# ATmega.net
KiCad netlist of a schematic drawn in Altium Designer
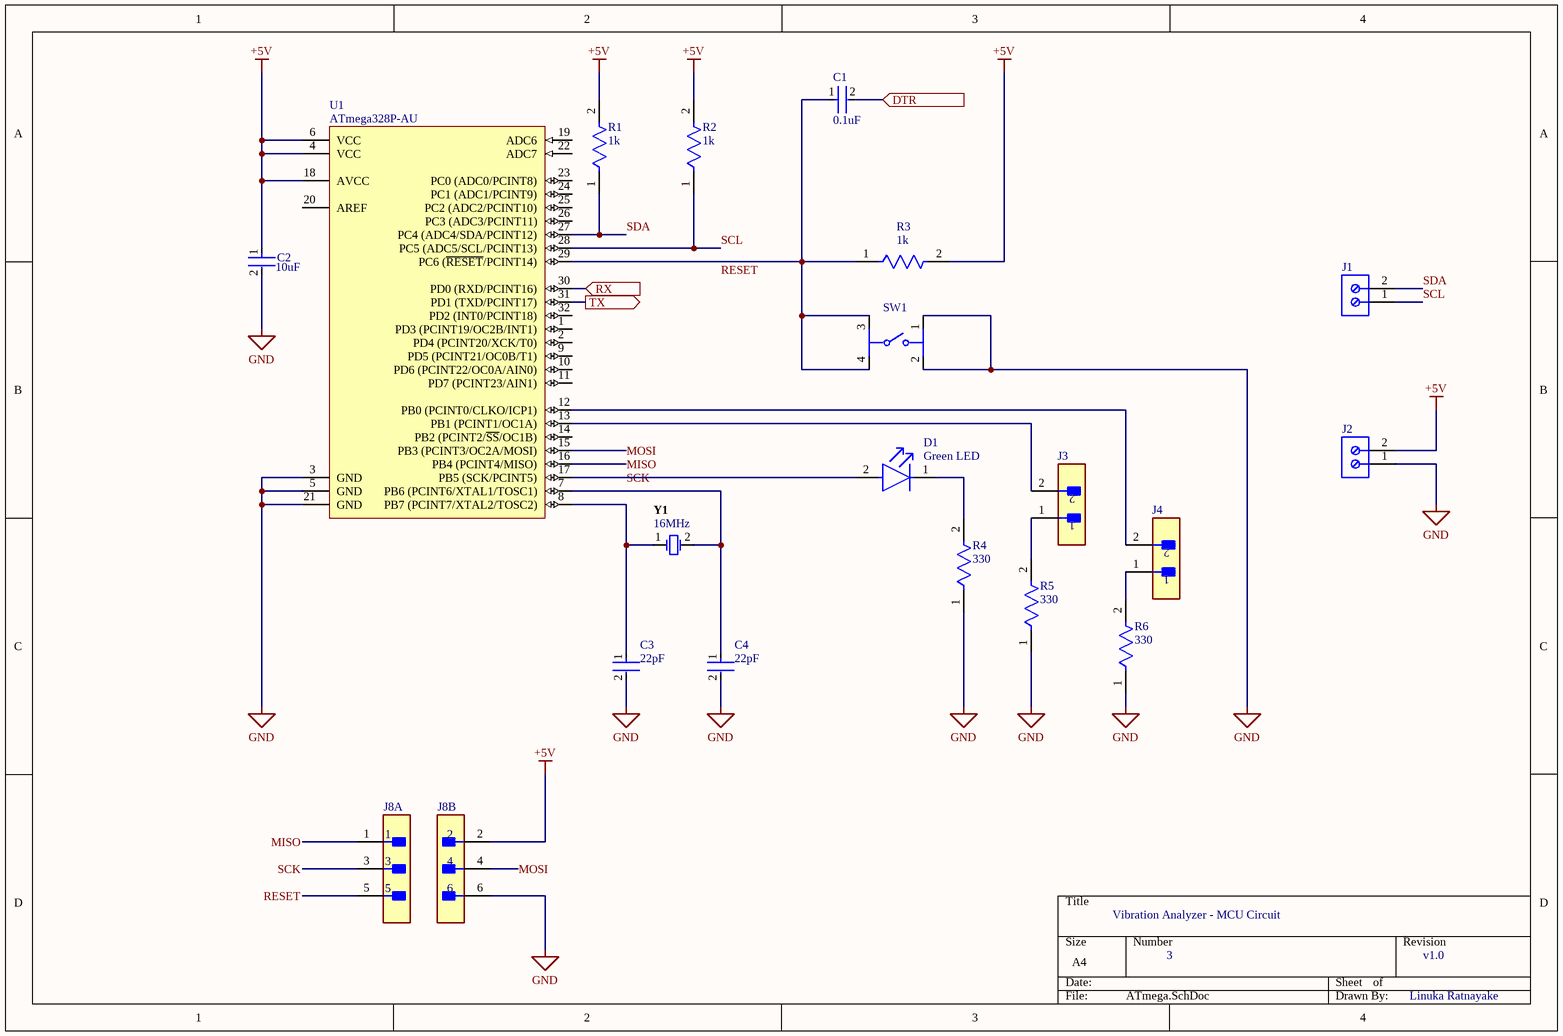
[diagram p0: ATmega.SchDoc]

(export (version "E")
  (design (tool "Eeschema 10.0.6"))
  (components
    (comp (ref "C1")
      (value "GRM31M1X1H104JA01L")
      (footprint "FP-GRM31M-0_15-IPC_A")
      (fields
        (field (name "VOLTAGE") "50V")
        (field (name "TOLERANCE") "5%")
        (field (name "CAPACITANCE") "0.1uF")
      )
      (libsource (lib "Altium Content Vault") (part "b4654b650e69147ec39a6b967a45e02"))
    )
    (comp (ref "C2")
      (value "GRM31M1X1H104JA01L")
      (footprint "FP-GRM31M-0_15-IPC_A")
      (fields
        (field (name "VOLTAGE") "50V")
        (field (name "TOLERANCE") "5%")
        (field (name "CAPACITANCE") "10uF")
      )
      (libsource (lib "Altium Content Vault") (part "b4654b650e69147ec39a6b967a45e02"))
    )
    (comp (ref "C3")
      (value "GRM31M1X1H104JA01L")
      (footprint "FP-GRM31M-0_15-IPC_A")
      (fields
        (field (name "VOLTAGE") "50V")
        (field (name "TOLERANCE") "5%")
        (field (name "CAPACITANCE") "22pF")
      )
      (libsource (lib "Altium Content Vault") (part "b4654b650e69147ec39a6b967a45e02"))
    )
    (comp (ref "C4")
      (value "GRM31M1X1H104JA01L")
      (footprint "FP-GRM31M-0_15-IPC_A")
      (fields
        (field (name "VOLTAGE") "50V")
        (field (name "TOLERANCE") "5%")
        (field (name "CAPACITANCE") "22pF")
      )
      (libsource (lib "Altium Content Vault") (part "b4654b650e69147ec39a6b967a45e02"))
    )
    (comp (ref "D1")
      (value "HSMG-C150")
      (footprint "FP-HSMG-C150-MFG")
      (description "LED GREEN DIFFUSED 1206 SMD")
      (fields
        (field (name "MANUFACTURER") "Broadcom")
        (field (name "OCTOPART") "https://octopart.com/hsmg-c150-broadcom-71131304")
        (field (name "COLOR") "Green LED")
      )
      (libsource (lib "Altium Content Vault") (part "8706943c75ba83719d021d2fdc84c58"))
    )
    (comp (ref "J1")
      (value "691214110002")
      (footprint "691214110002")
      (fields (field (name "VOLTAGE") "300V"))
      (libsource (lib "Altium Content Vault") (part "TBL - 1R - 02P - Screw"))
    )
    (comp (ref "J2")
      (value "691214110002")
      (footprint "691214110002")
      (fields (field (name "VOLTAGE") "300V"))
      (libsource (lib "Altium Content Vault") (part "TBL - 1R - 02P - Screw"))
    )
    (comp (ref "J3")
      (value "B2B-XH-A(LF)(SN)")
      (footprint "FP-B2B-XH-A_LF_SN-MFG")
      (description "CONN HEADER VERT 2POS 2.5MM")
      (libsource (lib "Altium Content Vault") (part "3bc925449376181038e59eaffc5286c"))
    )
    (comp (ref "J4")
      (value "B2B-XH-A(LF)(SN)")
      (footprint "FP-B2B-XH-A_LF_SN-MFG")
      (description "CONN HEADER VERT 2POS 2.5MM")
      (libsource (lib "Altium Content Vault") (part "3bc925449376181038e59eaffc5286c"))
    )
    (comp (ref "J8")
      (value "M20-9980346")
      (footprint "FP-M20-9980346-MFG")
      (description "2.54mm Pitch 6 Way 2 Row Straight PCB Header, Solder Termination, 3A")
      (fields (field (name "MANUFACTURER") "Harwin"))
      (libsource (lib "") (part "2654a11fb13586ecb194516b1c997bc_1"))
    )
    (comp (ref "R1")
      (value "MCR18EZPF30R0")
      (footprint "FP-MCR18-IPC_B")
      (description "Thick Film Chip Resistor, 1206, 30Ω, 1%, 100ppm/°C, 0.25W, 200V")
      (fields (field (name "RESISTANCE") "1k") (field (name "TOLERANCE") "1%"))
      (libsource (lib "Altium Content Vault") (part "1029c3af85768c4190bb7ad29bc67b5"))
    )
    (comp (ref "R2")
      (value "MCR18EZPF30R0")
      (footprint "FP-MCR18-IPC_B")
      (description "Thick Film Chip Resistor, 1206, 30Ω, 1%, 100ppm/°C, 0.25W, 200V")
      (fields (field (name "RESISTANCE") "1k") (field (name "TOLERANCE") "1%"))
      (libsource (lib "Altium Content Vault") (part "1029c3af85768c4190bb7ad29bc67b5"))
    )
    (comp (ref "R3")
      (value "MCR18EZPF30R0")
      (footprint "FP-MCR18-IPC_B")
      (description "Thick Film Chip Resistor, 1206, 30Ω, 1%, 100ppm/°C, 0.25W, 200V")
      (fields (field (name "RESISTANCE") "1k") (field (name "TOLERANCE") "1%"))
      (libsource (lib "Altium Content Vault") (part "1029c3af85768c4190bb7ad29bc67b5"))
    )
    (comp (ref "R4")
      (value "MCR18EZPF30R0")
      (footprint "FP-MCR18-IPC_B")
      (description "Thick Film Chip Resistor, 1206, 30Ω, 1%, 100ppm/°C, 0.25W, 200V")
      (fields (field (name "RESISTANCE") "330") (field (name "TOLERANCE") "1%"))
      (libsource (lib "Altium Content Vault") (part "1029c3af85768c4190bb7ad29bc67b5"))
    )
    (comp (ref "R5")
      (value "MCR18EZPF30R0")
      (footprint "FP-MCR18-IPC_B")
      (description "Thick Film Chip Resistor, 1206, 30Ω, 1%, 100ppm/°C, 0.25W, 200V")
      (fields (field (name "RESISTANCE") "330") (field (name "TOLERANCE") "1%"))
      (libsource (lib "Altium Content Vault") (part "1029c3af85768c4190bb7ad29bc67b5"))
    )
    (comp (ref "R6")
      (value "MCR18EZPF30R0")
      (footprint "FP-MCR18-IPC_B")
      (description "Thick Film Chip Resistor, 1206, 30Ω, 1%, 100ppm/°C, 0.25W, 200V")
      (fields (field (name "RESISTANCE") "330") (field (name "TOLERANCE") "1%"))
      (libsource (lib "Altium Content Vault") (part "1029c3af85768c4190bb7ad29bc67b5"))
    )
    (comp (ref "SW1")
      (value "PTS645SM43SMTR92LFS")
      (footprint "FP-PTS645SM43SMTR92LFS-MFG")
      (description "SWITCH TACTILE SPST-NO 0.05A 12V")
      (libsource (lib "Altium Content Vault") (part "1adf0dd01260c80cf25a44bfd6b99ba"))
    )
    (comp (ref "U1")
      (value "ATmega328P-AU")
      (footprint "32A_M")
      (libsource (lib "Altium Content Vault") (part "MC-8B-ATM48-SQ32"))
    )
    (comp (ref "Y1")
      (value "FOXSLF/160-20")
      (footprint "FOX-FOXSLF160-20")
      (description "Resistance Weld Thru-Hole Crystal, 16 MHz, -20 to 70 degC, 2-Pin THD, RoHS, Bulk")
      (fields (field (name "TOLERANCE") "1%") (field (name "FREQUENCY") "16MHz"))
      (libsource (lib "Altium Content Vault") (part "XTAL-1-2-2"))
    )
  )
  (nets
    (net (code "1") (name "+5V") (class "Default")
      (node (ref "C2") (pin "1") (pinfunction "1_1") (pintype "passive"))
      (node (ref "J2") (pin "2") (pinfunction "2_2") (pintype "passive"))
      (node (ref "J8") (pin "2") (pinfunction "2_2") (pintype "passive"))
      (node (ref "R1") (pin "2") (pinfunction "2_2") (pintype "passive"))
      (node (ref "R2") (pin "2") (pinfunction "2_2") (pintype "passive"))
      (node (ref "R3") (pin "2") (pinfunction "2_2") (pintype "passive"))
      (node (ref "U1") (pin "18") (pinfunction "AVCC_18") (pintype "power_in"))
      (node (ref "U1") (pin "4") (pinfunction "VCC_4") (pintype "power_in"))
      (node (ref "U1") (pin "6") (pinfunction "VCC_6") (pintype "power_in"))
    )
    (net (code "2") (name "/DTR") (class "Default")
      (node (ref "C1") (pin "2") (pinfunction "2_2") (pintype "passive"))
    )
    (net (code "3") (name "/MISO") (class "Default")
      (node (ref "J8") (pin "1") (pinfunction "1_1") (pintype "passive"))
      (node (ref "U1") (pin "16") (pinfunction "PB4_(PCINT4/MISO)_16") (pintype "bidirectional"))
    )
    (net (code "4") (name "/MOSI") (class "Default")
      (node (ref "J8") (pin "4") (pinfunction "4_4") (pintype "passive"))
      (node (ref "U1") (pin "15") (pinfunction "PB3_(PCINT3/OC2A/MOSI)_15") (pintype "bidirectional"))
    )
    (net (code "5") (name "/RESET") (class "Default")
      (node (ref "C1") (pin "1") (pinfunction "1_1") (pintype "passive"))
      (node (ref "J8") (pin "5") (pinfunction "5_5") (pintype "passive"))
      (node (ref "R3") (pin "1") (pinfunction "1_1") (pintype "passive"))
      (node (ref "SW1") (pin "3") (pinfunction "3_3") (pintype "passive"))
      (node (ref "SW1") (pin "4") (pinfunction "4_4") (pintype "passive"))
      (node (ref "U1") (pin "29") (pinfunction "PC6_(~{RESET}/PCINT14)_29") (pintype "bidirectional"))
    )
    (net (code "6") (name "/RX") (class "Default")
      (node (ref "U1") (pin "30") (pinfunction "PD0_(RXD/PCINT16)_30") (pintype "bidirectional"))
    )
    (net (code "7") (name "/SCK") (class "Default")
      (node (ref "D1") (pin "2") (pinfunction "A_2") (pintype "passive"))
      (node (ref "J8") (pin "3") (pinfunction "3_3") (pintype "passive"))
      (node (ref "U1") (pin "17") (pinfunction "PB5_(SCK/PCINT5)_17") (pintype "bidirectional"))
    )
    (net (code "8") (name "/SCL") (class "Default")
      (node (ref "J1") (pin "1") (pinfunction "1_1") (pintype "passive"))
      (node (ref "R2") (pin "1") (pinfunction "1_1") (pintype "passive"))
      (node (ref "U1") (pin "28") (pinfunction "PC5_(ADC5/SCL/PCINT13)_28") (pintype "bidirectional"))
    )
    (net (code "9") (name "/SDA") (class "Default")
      (node (ref "J1") (pin "2") (pinfunction "2_2") (pintype "passive"))
      (node (ref "R1") (pin "1") (pinfunction "1_1") (pintype "passive"))
      (node (ref "U1") (pin "27") (pinfunction "PC4_(ADC4/SDA/PCINT12)_27") (pintype "bidirectional"))
    )
    (net (code "10") (name "/TX") (class "Default")
      (node (ref "U1") (pin "31") (pinfunction "PD1_(TXD/PCINT17)_31") (pintype "bidirectional"))
    )
    (net (code "11") (name "GND") (class "Default")
      (node (ref "C2") (pin "2") (pinfunction "2_2") (pintype "passive"))
      (node (ref "C3") (pin "2") (pinfunction "2_2") (pintype "passive"))
      (node (ref "C4") (pin "2") (pinfunction "2_2") (pintype "passive"))
      (node (ref "J2") (pin "1") (pinfunction "1_1") (pintype "passive"))
      (node (ref "J8") (pin "6") (pinfunction "6_6") (pintype "passive"))
      (node (ref "R4") (pin "1") (pinfunction "1_1") (pintype "passive"))
      (node (ref "R5") (pin "1") (pinfunction "1_1") (pintype "passive"))
      (node (ref "R6") (pin "1") (pinfunction "1_1") (pintype "passive"))
      (node (ref "SW1") (pin "1") (pinfunction "1_1") (pintype "passive"))
      (node (ref "SW1") (pin "2") (pinfunction "2_2") (pintype "passive"))
      (node (ref "U1") (pin "21") (pinfunction "GND_21") (pintype "power_in"))
      (node (ref "U1") (pin "3") (pinfunction "GND_3") (pintype "power_in"))
      (node (ref "U1") (pin "5") (pinfunction "GND_5") (pintype "power_in"))
    )
    (net (code "12") (name "Net-(D1-C)") (class "Default")
      (node (ref "D1") (pin "1") (pinfunction "C_1") (pintype "passive"))
      (node (ref "R4") (pin "2") (pinfunction "2_2") (pintype "passive"))
    )
    (net (code "13") (name "Net-(J3-Pad1)") (class "Default")
      (node (ref "J3") (pin "1") (pinfunction "1_1") (pintype "passive"))
      (node (ref "R5") (pin "2") (pinfunction "2_2") (pintype "passive"))
    )
    (net (code "14") (name "Net-(J4-Pad1)") (class "Default")
      (node (ref "J4") (pin "1") (pinfunction "1_1") (pintype "passive"))
      (node (ref "R6") (pin "2") (pinfunction "2_2") (pintype "passive"))
    )
    (net (code "15") (name "Net-(U1-PB0_(PCINT0{slash}CLKO{slash}ICP1))") (class "Default")
      (node (ref "J4") (pin "2") (pinfunction "2_2") (pintype "passive"))
      (node (ref "U1") (pin "12") (pinfunction "PB0_(PCINT0/CLKO/ICP1)_12") (pintype "bidirectional"))
    )
    (net (code "16") (name "Net-(U1-PB1_(PCINT1{slash}OC1A))") (class "Default")
      (node (ref "J3") (pin "2") (pinfunction "2_2") (pintype "passive"))
      (node (ref "U1") (pin "13") (pinfunction "PB1_(PCINT1/OC1A)_13") (pintype "bidirectional"))
    )
    (net (code "17") (name "Net-(U1-PB6_(PCINT6{slash}XTAL1{slash}TOSC1))") (class "Default")
      (node (ref "C4") (pin "1") (pinfunction "1_1") (pintype "passive"))
      (node (ref "U1") (pin "7") (pinfunction "PB6_(PCINT6/XTAL1/TOSC1)_7") (pintype "bidirectional"))
      (node (ref "Y1") (pin "2") (pinfunction "2_2") (pintype "passive"))
    )
    (net (code "18") (name "Net-(U1-PB7_(PCINT7{slash}XTAL2{slash}TOSC2))") (class "Default")
      (node (ref "C3") (pin "1") (pinfunction "1_1") (pintype "passive"))
      (node (ref "U1") (pin "8") (pinfunction "PB7_(PCINT7/XTAL2/TOSC2)_8") (pintype "bidirectional"))
      (node (ref "Y1") (pin "1") (pinfunction "1_1") (pintype "passive"))
    )
    (net (code "19") (name "unconnected-(U1-ADC6-Pad19)") (class "Default")
      (node (ref "U1") (pin "19") (pinfunction "ADC6_19") (pintype "input"))
    )
    (net (code "20") (name "unconnected-(U1-ADC7-Pad22)") (class "Default")
      (node (ref "U1") (pin "22") (pinfunction "ADC7_22") (pintype "input"))
    )
    (net (code "21") (name "unconnected-(U1-AREF-Pad20)") (class "Default")
      (node (ref "U1") (pin "20") (pinfunction "AREF_20") (pintype "passive"))
    )
    (net (code "22") (name "unconnected-(U1-PB2_(PCINT2{slash}~{SS}{slash}OC1B)-Pad14)") (class "Default")
      (node (ref "U1") (pin "14") (pinfunction "PB2_(PCINT2/~{SS}/OC1B)_14") (pintype "bidirectional"))
    )
    (net (code "23") (name "unconnected-(U1-PC0_(ADC0{slash}PCINT8)-Pad23)") (class "Default")
      (node (ref "U1") (pin "23") (pinfunction "PC0_(ADC0/PCINT8)_23") (pintype "bidirectional"))
    )
    (net (code "24") (name "unconnected-(U1-PC1_(ADC1{slash}PCINT9)-Pad24)") (class "Default")
      (node (ref "U1") (pin "24") (pinfunction "PC1_(ADC1/PCINT9)_24") (pintype "bidirectional"))
    )
    (net (code "25") (name "unconnected-(U1-PC2_(ADC2{slash}PCINT10)-Pad25)") (class "Default")
      (node (ref "U1") (pin "25") (pinfunction "PC2_(ADC2/PCINT10)_25") (pintype "bidirectional"))
    )
    (net (code "26") (name "unconnected-(U1-PC3_(ADC3{slash}PCINT11)-Pad26)") (class "Default")
      (node (ref "U1") (pin "26") (pinfunction "PC3_(ADC3/PCINT11)_26") (pintype "bidirectional"))
    )
    (net (code "27") (name "unconnected-(U1-PD2_(INT0{slash}PCINT18)-Pad32)") (class "Default")
      (node (ref "U1") (pin "32") (pinfunction "PD2_(INT0/PCINT18)_32") (pintype "bidirectional"))
    )
    (net (code "28") (name "unconnected-(U1-PD3_(PCINT19{slash}OC2B{slash}INT1)-Pad1)") (class "Default")
      (node (ref "U1") (pin "1") (pinfunction "PD3_(PCINT19/OC2B/INT1)_1") (pintype "bidirectional"))
    )
    (net (code "29") (name "unconnected-(U1-PD4_(PCINT20{slash}XCK{slash}T0)-Pad2)") (class "Default")
      (node (ref "U1") (pin "2") (pinfunction "PD4_(PCINT20/XCK/T0)_2") (pintype "bidirectional"))
    )
    (net (code "30") (name "unconnected-(U1-PD5_(PCINT21{slash}OC0B{slash}T1)-Pad9)") (class "Default")
      (node (ref "U1") (pin "9") (pinfunction "PD5_(PCINT21/OC0B/T1)_9") (pintype "bidirectional"))
    )
    (net (code "31") (name "unconnected-(U1-PD6_(PCINT22{slash}OC0A{slash}AIN0)-Pad10)") (class "Default")
      (node (ref "U1") (pin "10") (pinfunction "PD6_(PCINT22/OC0A/AIN0)_10") (pintype "bidirectional"))
    )
    (net (code "32") (name "unconnected-(U1-PD7_(PCINT23{slash}AIN1)-Pad11)") (class "Default")
      (node (ref "U1") (pin "11") (pinfunction "PD7_(PCINT23/AIN1)_11") (pintype "bidirectional"))
    )
  )
)
